# cme_schematic.net
KiCad netlist of a schematic drawn in EAGLE
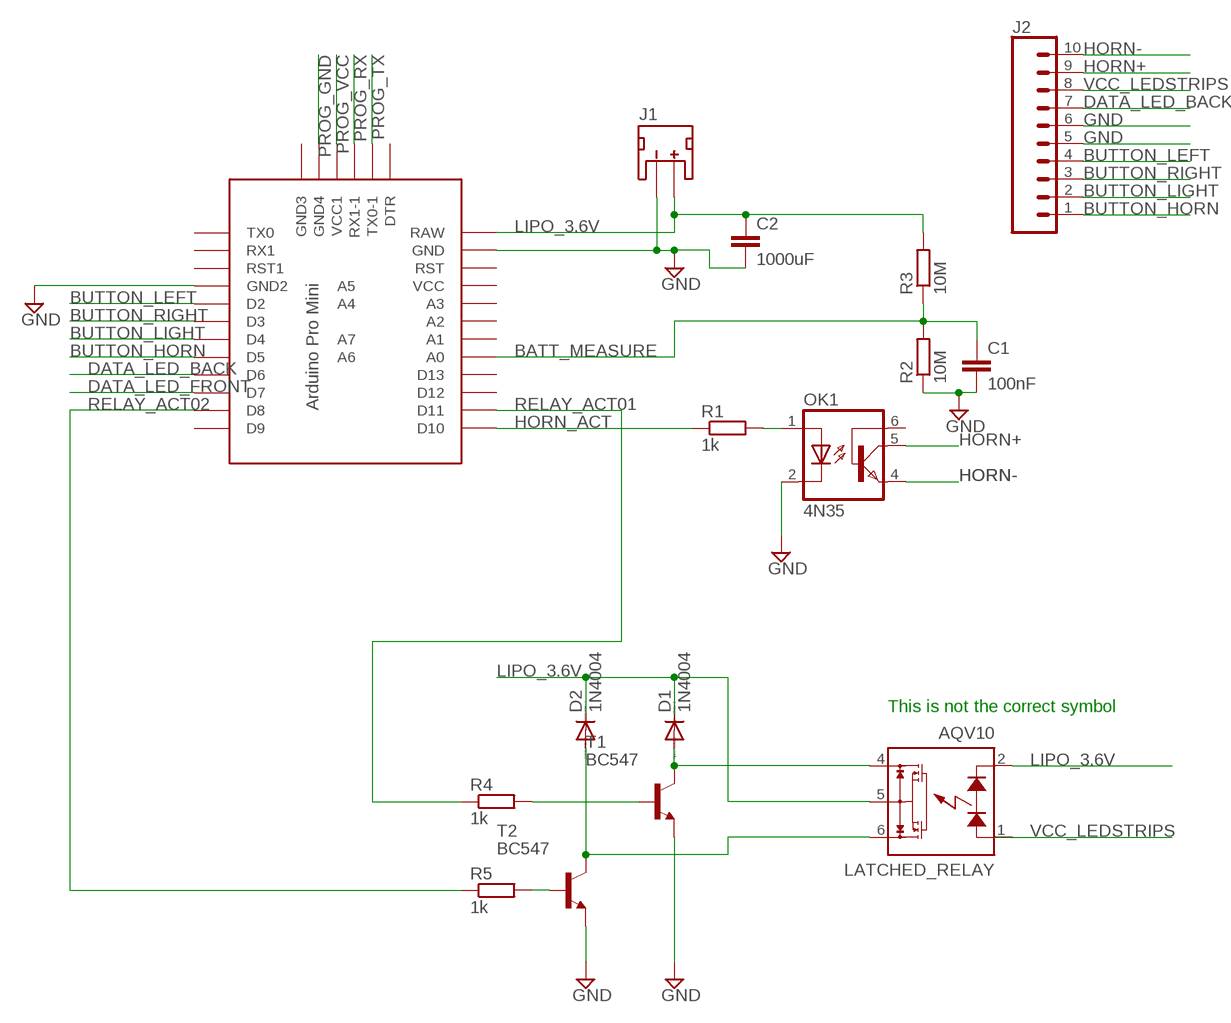
[diagram p0: schematic, sheet 1]

(export (version "E")
  (design (tool "Eeschema 10.0.6"))
  (components
    (comp (ref "C1")
      (value "100nF")
      (footprint "eagle-import:C025-025X050")
      (libsource (lib "eagle-import") (part "C-EU025-025X050"))
    )
    (comp (ref "C2")
      (value "1000uF")
      (footprint "eagle-import:C025-025X050")
      (libsource (lib "eagle-import") (part "C-EU025-025X050"))
    )
    (comp (ref "D1")
      (value "1N4004")
      (footprint "eagle-import:DO41-10")
      (libsource (lib "eagle-import") (part "1N4004"))
    )
    (comp (ref "D2")
      (value "1N4004")
      (footprint "eagle-import:DO41-10")
      (libsource (lib "eagle-import") (part "1N4004"))
    )
    (comp (ref "J1")
      (value "JST_2MM_MALE")
      (footprint "eagle-import:JST-2-SMD")
      (libsource (lib "eagle-import") (part "JST_2MM_MALE"))
    )
    (comp (ref "J2")
      (value "CONN_10\"")
      (footprint "eagle-import:1X10")
      (libsource (lib "eagle-import") (part "CONN_10{dblquote}"))
    )
    (comp (ref "LATCHED_RELAY")
      (value "AQV10")
      (footprint "eagle-import:DIL06")
      (fields (field (name "MF") "AROMAT/ MATSUSHITA") (field (name "MPN") "AQV102"))
      (libsource (lib "eagle-import") (part "AQV10"))
    )
    (comp (ref "OK1")
      (value "4N35")
      (footprint "eagle-import:DIL06")
      (fields (field (name "MF") "FAIRCHILD SEMICONDUCTOR"))
      (libsource (lib "eagle-import") (part "4N35"))
    )
    (comp (ref "R1")
      (value "1k")
      (footprint "eagle-import:0617_22")
      (libsource (lib "eagle-import") (part "R-EU_0617/22"))
    )
    (comp (ref "R2")
      (value "10M")
      (footprint "eagle-import:0617_22")
      (libsource (lib "eagle-import") (part "R-EU_0617/22"))
    )
    (comp (ref "R3")
      (value "10M")
      (footprint "eagle-import:0617_22")
      (libsource (lib "eagle-import") (part "R-EU_0617/22"))
    )
    (comp (ref "R4")
      (value "1k")
      (footprint "eagle-import:0617_22")
      (libsource (lib "eagle-import") (part "R-EU_0617/22"))
    )
    (comp (ref "R5")
      (value "1k")
      (footprint "eagle-import:0617_22")
      (libsource (lib "eagle-import") (part "R-EU_0617/22"))
    )
    (comp (ref "T1")
      (value "BC547")
      (footprint "eagle-import:TO92")
      (libsource (lib "eagle-import") (part "BC547"))
    )
    (comp (ref "T2")
      (value "BC547")
      (footprint "eagle-import:TO92")
      (libsource (lib "eagle-import") (part "BC547"))
    )
    (comp (ref "U$1")
      (value "PRO-MINI-2")
      (footprint "eagle-import:PRO-MINI-2")
      (libsource (lib "eagle-import") (part "PRO-MINI-2"))
    )
  )
  (nets
    (net (code "1") (name "/BATT_MEASURE") (class "Default")
      (node (ref "C1") (pin "1") (pinfunction "1_1") (pintype "passive"))
      (node (ref "R2") (pin "2") (pinfunction "2_2") (pintype "passive"))
      (node (ref "R3") (pin "1") (pinfunction "1_1") (pintype "passive"))
      (node (ref "U$1") (pin "A0") (pinfunction "A0_A0") (pintype "bidirectional"))
    )
    (net (code "2") (name "/BUTTON_HORN") (class "Default")
      (node (ref "J2") (pin "1") (pinfunction "1_1") (pintype "passive"))
      (node (ref "U$1") (pin "D5") (pinfunction "D5_D5") (pintype "bidirectional"))
    )
    (net (code "3") (name "/BUTTON_LEFT") (class "Default")
      (node (ref "J2") (pin "4") (pinfunction "4_4") (pintype "passive"))
      (node (ref "U$1") (pin "D2") (pinfunction "D2_D2") (pintype "bidirectional"))
    )
    (net (code "4") (name "/BUTTON_LIGHT") (class "Default")
      (node (ref "J2") (pin "2") (pinfunction "2_2") (pintype "passive"))
      (node (ref "U$1") (pin "D4") (pinfunction "D4_D4") (pintype "bidirectional"))
    )
    (net (code "5") (name "/BUTTON_RIGHT") (class "Default")
      (node (ref "J2") (pin "3") (pinfunction "3_3") (pintype "passive"))
      (node (ref "U$1") (pin "D3") (pinfunction "D3_D3") (pintype "bidirectional"))
    )
    (net (code "6") (name "/DATA_LED_BACK") (class "Default")
      (node (ref "J2") (pin "7") (pinfunction "7_7") (pintype "passive"))
      (node (ref "U$1") (pin "D6") (pinfunction "D6_D6") (pintype "bidirectional"))
    )
    (net (code "7") (name "/DATA_LED_FRONT") (class "Default")
      (node (ref "U$1") (pin "D7") (pinfunction "D7_D7") (pintype "bidirectional"))
    )
    (net (code "8") (name "/HORN+") (class "Default")
      (node (ref "OK1") (pin "5") (pinfunction "COL_5") (pintype "passive"))
    )
    (net (code "9") (name "/HORN-") (class "Default")
      (node (ref "OK1") (pin "4") (pinfunction "EMI_4") (pintype "passive"))
    )
    (net (code "10") (name "/HORN_ACT") (class "Default")
      (node (ref "R1") (pin "1") (pinfunction "1_1") (pintype "passive"))
      (node (ref "U$1") (pin "D10") (pinfunction "D10_D10") (pintype "bidirectional"))
    )
    (net (code "11") (name "/LIPO_3.6V") (class "Default")
      (node (ref "C2") (pin "1") (pinfunction "1_1") (pintype "passive"))
      (node (ref "D1") (pin "C") (pinfunction "C_C") (pintype "passive"))
      (node (ref "D2") (pin "C") (pinfunction "C_C") (pintype "passive"))
      (node (ref "J1") (pin "2") (pinfunction "+_2") (pintype "bidirectional"))
      (node (ref "LATCHED_RELAY") (pin "2") (pinfunction "K_2") (pintype "passive"))
      (node (ref "LATCHED_RELAY") (pin "5") (pinfunction "S_5") (pintype "passive"))
      (node (ref "R3") (pin "2") (pinfunction "2_2") (pintype "passive"))
      (node (ref "U$1") (pin "RAW") (pinfunction "RAW_RAW") (pintype "bidirectional"))
    )
    (net (code "12") (name "/PROG_GND") (class "Default")
      (node (ref "U$1") (pin "GND3") (pinfunction "GND4_GND3") (pintype "bidirectional"))
    )
    (net (code "13") (name "/PROG_RX") (class "Default")
      (node (ref "U$1") (pin "RX1-1") (pinfunction "RX1-1_RX1-1") (pintype "bidirectional"))
    )
    (net (code "14") (name "/PROG_TX") (class "Default")
      (node (ref "U$1") (pin "TX0-1") (pinfunction "TX0-1_TX0-1") (pintype "bidirectional"))
    )
    (net (code "15") (name "/PROG_VCC") (class "Default")
      (node (ref "U$1") (pin "VCC1") (pinfunction "VCC1_VCC1") (pintype "bidirectional"))
    )
    (net (code "16") (name "/RELAY_ACT01") (class "Default")
      (node (ref "R4") (pin "1") (pinfunction "1_1") (pintype "passive"))
      (node (ref "U$1") (pin "D11") (pinfunction "D11_D11") (pintype "bidirectional"))
    )
    (net (code "17") (name "/RELAY_ACT02") (class "Default")
      (node (ref "R5") (pin "1") (pinfunction "1_1") (pintype "passive"))
      (node (ref "U$1") (pin "D8") (pinfunction "D8_D8") (pintype "bidirectional"))
    )
    (net (code "18") (name "/VCC_LEDSTRIPS") (class "Default")
      (node (ref "J2") (pin "8") (pinfunction "8_8") (pintype "passive"))
      (node (ref "LATCHED_RELAY") (pin "1") (pinfunction "A_1") (pintype "passive"))
    )
    (net (code "19") (name "GND") (class "Default")
      (node (ref "C1") (pin "2") (pinfunction "2_2") (pintype "passive"))
      (node (ref "C2") (pin "2") (pinfunction "2_2") (pintype "passive"))
      (node (ref "J1") (pin "1") (pinfunction "-_1") (pintype "bidirectional"))
      (node (ref "J2") (pin "5") (pinfunction "5_5") (pintype "passive"))
      (node (ref "J2") (pin "6") (pinfunction "6_6") (pintype "passive"))
      (node (ref "OK1") (pin "2") (pinfunction "C_2") (pintype "passive"))
      (node (ref "R2") (pin "1") (pinfunction "1_1") (pintype "passive"))
      (node (ref "T1") (pin "1") (pinfunction "E_1") (pintype "passive"))
      (node (ref "T2") (pin "1") (pinfunction "E_1") (pintype "passive"))
      (node (ref "U$1") (pin "GND") (pinfunction "GND_GND") (pintype "bidirectional"))
      (node (ref "U$1") (pin "GND1") (pinfunction "GND2_GND1") (pintype "bidirectional"))
    )
    (net (code "20") (name "Net-(LATCHED_RELAY-D1)") (class "Default")
      (node (ref "D2") (pin "A") (pinfunction "A_A") (pintype "passive"))
      (node (ref "LATCHED_RELAY") (pin "6") (pinfunction "D1_6") (pintype "passive"))
      (node (ref "T2") (pin "3") (pinfunction "C_3") (pintype "passive"))
    )
    (net (code "21") (name "Net-(LATCHED_RELAY-D2)") (class "Default")
      (node (ref "D1") (pin "A") (pinfunction "A_A") (pintype "passive"))
      (node (ref "LATCHED_RELAY") (pin "4") (pinfunction "D2_4") (pintype "passive"))
      (node (ref "T1") (pin "3") (pinfunction "C_3") (pintype "passive"))
    )
    (net (code "22") (name "Net-(OK1-A)") (class "Default")
      (node (ref "OK1") (pin "1") (pinfunction "A_1") (pintype "passive"))
      (node (ref "R1") (pin "2") (pinfunction "2_2") (pintype "passive"))
    )
    (net (code "23") (name "Net-(T1-B)") (class "Default")
      (node (ref "R4") (pin "2") (pinfunction "2_2") (pintype "passive"))
      (node (ref "T1") (pin "2") (pinfunction "B_2") (pintype "passive"))
    )
    (net (code "24") (name "Net-(T2-B)") (class "Default")
      (node (ref "R5") (pin "2") (pinfunction "2_2") (pintype "passive"))
      (node (ref "T2") (pin "2") (pinfunction "B_2") (pintype "passive"))
    )
    (net (code "25") (name "unconnected-(J1-PAD1-PadNC1)") (class "Default")
      (node (ref "J1") (pin "NC1") (pinfunction "PAD1_NC1") (pintype "bidirectional"))
    )
    (net (code "26") (name "unconnected-(J1-PAD2-PadNC2)") (class "Default")
      (node (ref "J1") (pin "NC2") (pinfunction "PAD2_NC2") (pintype "bidirectional"))
    )
    (net (code "27") (name "unconnected-(J2-Pad9)") (class "Default")
      (node (ref "J2") (pin "9") (pinfunction "9_9") (pintype "passive"))
    )
    (net (code "28") (name "unconnected-(J2-Pad10)") (class "Default")
      (node (ref "J2") (pin "10") (pinfunction "10_10") (pintype "passive"))
    )
    (net (code "29") (name "unconnected-(OK1-BAS-Pad6)") (class "Default")
      (node (ref "OK1") (pin "6") (pinfunction "BAS_6") (pintype "passive"))
    )
    (net (code "30") (name "unconnected-(U$1-GND3-PadGND2)") (class "Default")
      (node (ref "U$1") (pin "GND2") (pinfunction "GND3_GND2") (pintype "bidirectional"))
    )
    (net (code "31") (name "unconnected-(U$1-PadA1)") (class "Default")
      (node (ref "U$1") (pin "A1") (pinfunction "A1_A1") (pintype "bidirectional"))
    )
    (net (code "32") (name "unconnected-(U$1-PadA2)") (class "Default")
      (node (ref "U$1") (pin "A2") (pinfunction "A2_A2") (pintype "bidirectional"))
    )
    (net (code "33") (name "unconnected-(U$1-PadA3)") (class "Default")
      (node (ref "U$1") (pin "A3") (pinfunction "A3_A3") (pintype "bidirectional"))
    )
    (net (code "34") (name "unconnected-(U$1-PadA4)") (class "Default")
      (node (ref "U$1") (pin "A4") (pinfunction "A4_A4") (pintype "bidirectional"))
    )
    (net (code "35") (name "unconnected-(U$1-PadA5)") (class "Default")
      (node (ref "U$1") (pin "A5") (pinfunction "A5_A5") (pintype "bidirectional"))
    )
    (net (code "36") (name "unconnected-(U$1-PadA6)") (class "Default")
      (node (ref "U$1") (pin "A6") (pinfunction "A6_A6") (pintype "bidirectional"))
    )
    (net (code "37") (name "unconnected-(U$1-PadA7)") (class "Default")
      (node (ref "U$1") (pin "A7") (pinfunction "A7_A7") (pintype "bidirectional"))
    )
    (net (code "38") (name "unconnected-(U$1-PadD9)") (class "Default")
      (node (ref "U$1") (pin "D9") (pinfunction "D9_D9") (pintype "bidirectional"))
    )
    (net (code "39") (name "unconnected-(U$1-PadD12)") (class "Default")
      (node (ref "U$1") (pin "D12") (pinfunction "D12_D12") (pintype "bidirectional"))
    )
    (net (code "40") (name "unconnected-(U$1-PadD13)") (class "Default")
      (node (ref "U$1") (pin "D13") (pinfunction "D13_D13") (pintype "bidirectional"))
    )
    (net (code "41") (name "unconnected-(U$1-PadDTR)") (class "Default")
      (node (ref "U$1") (pin "DTR") (pinfunction "DTR_DTR") (pintype "bidirectional"))
    )
    (net (code "42") (name "unconnected-(U$1-PadRST)") (class "Default")
      (node (ref "U$1") (pin "RST") (pinfunction "RST_RST") (pintype "bidirectional"))
    )
    (net (code "43") (name "unconnected-(U$1-PadRST1)") (class "Default")
      (node (ref "U$1") (pin "RST1") (pinfunction "RST1_RST1") (pintype "bidirectional"))
    )
    (net (code "44") (name "unconnected-(U$1-PadRX1)") (class "Default")
      (node (ref "U$1") (pin "RX1") (pinfunction "RX1_RX1") (pintype "bidirectional"))
    )
    (net (code "45") (name "unconnected-(U$1-PadTX0)") (class "Default")
      (node (ref "U$1") (pin "TX0") (pinfunction "TX0_TX0") (pintype "bidirectional"))
    )
    (net (code "46") (name "unconnected-(U$1-PadVCC)") (class "Default")
      (node (ref "U$1") (pin "VCC") (pinfunction "VCC_VCC") (pintype "bidirectional"))
    )
  )
)
